# Esquema20.net
KiCad netlist of a schematic drawn in EAGLE
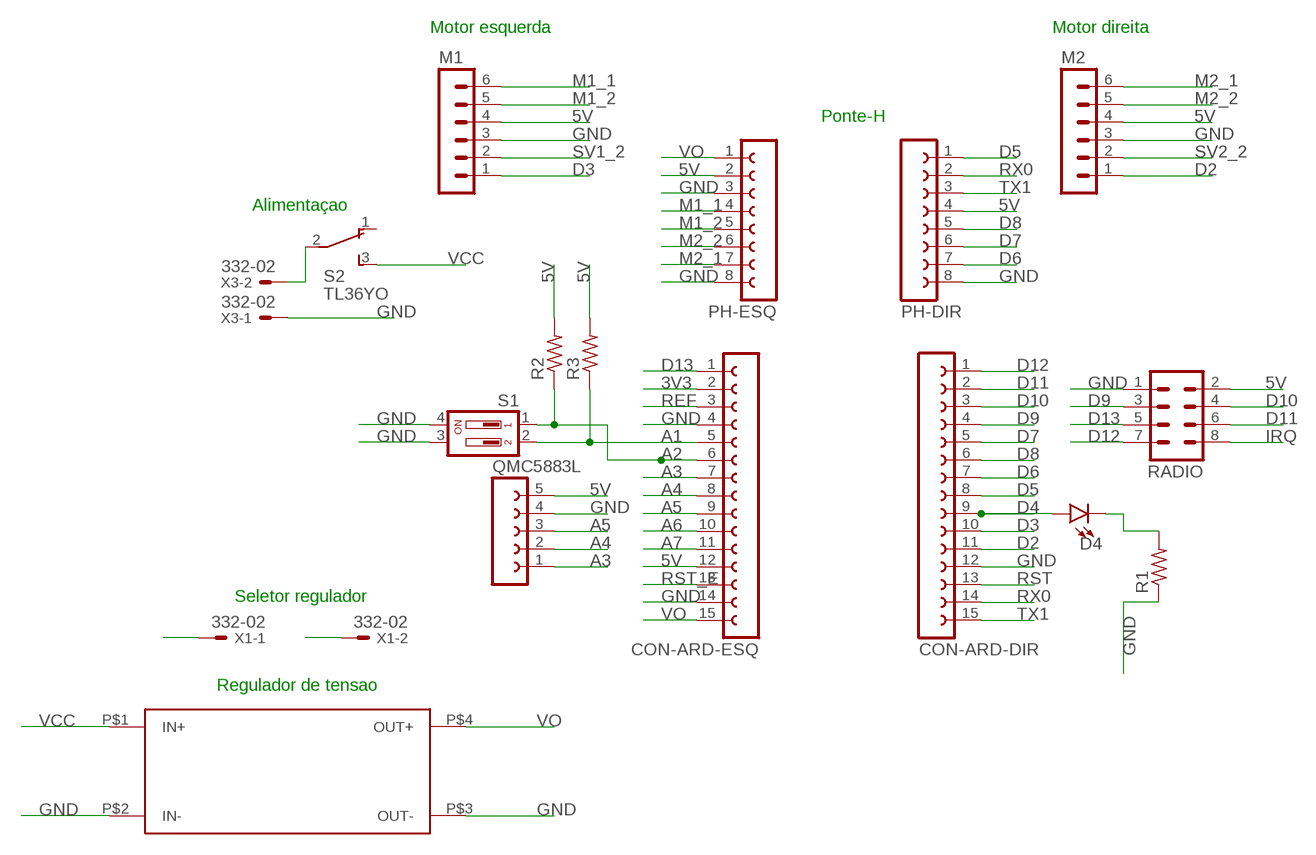
[diagram p0: schematic, sheet 1]

(export (version "E")
  (design (tool "Eeschema 10.0.6"))
  (components
    (comp (ref "CON-ARD-DIR")
      (value "FE15-1")
      (footprint "eagle-import:FE15")
      (libsource (lib "eagle-import") (part "FE15-1"))
    )
    (comp (ref "CON-ARD-ESQ")
      (value "FE15-1")
      (footprint "eagle-import:FE15")
      (fields (field (name "SPICEPREFIX") "X"))
      (libsource (lib "eagle-import") (part "FE15-1"))
    )
    (comp (ref "D4")
      (value "LED-3MM-NO_SILK")
      (footprint "eagle-import:LED_3MM-NS")
      (libsource (lib "eagle-import") (part "LED-3MM-NO_SILK"))
    )
    (comp (ref "M1")
      (value "MA06-1")
      (footprint "eagle-import:MA06-1")
      (libsource (lib "eagle-import") (part "MA06-1"))
    )
    (comp (ref "M2")
      (value "MA06-1")
      (footprint "eagle-import:MA06-1")
      (libsource (lib "eagle-import") (part "MA06-1"))
    )
    (comp (ref "PH-DIR")
      (value "FE08-1")
      (footprint "eagle-import:FE08")
      (libsource (lib "eagle-import") (part "FE08-1"))
    )
    (comp (ref "PH-ESQ")
      (value "FE08-1")
      (footprint "eagle-import:FE08")
      (libsource (lib "eagle-import") (part "FE08-1"))
    )
    (comp (ref "QMC5883L")
      (value "FE05W")
      (footprint "eagle-import:FE05W")
      (libsource (lib "eagle-import") (part "FE05W"))
    )
    (comp (ref "R1")
      (value "R-US_0207/12")
      (footprint "eagle-import:0207_12")
      (libsource (lib "eagle-import") (part "R-US_0207/12"))
    )
    (comp (ref "R2")
      (value "R-US_0207/12")
      (footprint "eagle-import:0207_12")
      (libsource (lib "eagle-import") (part "R-US_0207/12"))
    )
    (comp (ref "R3")
      (value "R-US_0207/12")
      (footprint "eagle-import:0207_12")
      (libsource (lib "eagle-import") (part "R-US_0207/12"))
    )
    (comp (ref "RADIO")
      (value "MA04-2")
      (footprint "eagle-import:MA04-2")
      (libsource (lib "eagle-import") (part "MA04-2"))
    )
    (comp (ref "S1")
      (value "DA02")
      (footprint "eagle-import:DA-02")
      (libsource (lib "eagle-import") (part "DA02"))
    )
    (comp (ref "S2")
      (value "TL36YO")
      (footprint "eagle-import:TL3XYO")
      (libsource (lib "eagle-import") (part "TL36YO"))
    )
    (comp (ref "U$1")
      (value "REGULADOR")
      (footprint "eagle-import:REGULADOR-FP")
      (libsource (lib "eagle-import") (part "REGULADOR"))
    )
    (comp (ref "X1")
      (value "332-02")
      (footprint "eagle-import:332-02")
      (libsource (lib "eagle-import") (part "332-02"))
    )
    (comp (ref "X3")
      (value "332-02")
      (footprint "eagle-import:332-02")
      (libsource (lib "eagle-import") (part "332-02"))
    )
  )
  (nets
    (net (code "1") (name "/3V3") (class "Default")
      (node (ref "CON-ARD-ESQ") (pin "2") (pinfunction "2_2") (pintype "passive"))
    )
    (net (code "2") (name "/5V") (class "Default")
      (node (ref "CON-ARD-ESQ") (pin "12") (pinfunction "12_12") (pintype "passive"))
      (node (ref "M1") (pin "4") (pinfunction "4_4") (pintype "passive"))
      (node (ref "M2") (pin "4") (pinfunction "4_4") (pintype "passive"))
      (node (ref "PH-DIR") (pin "4") (pinfunction "4_4") (pintype "passive"))
      (node (ref "PH-ESQ") (pin "2") (pinfunction "2_2") (pintype "passive"))
      (node (ref "QMC5883L") (pin "5") (pinfunction "5_5") (pintype "passive"))
      (node (ref "R2") (pin "2") (pinfunction "2_2") (pintype "passive"))
      (node (ref "R3") (pin "2") (pinfunction "2_2") (pintype "passive"))
      (node (ref "RADIO") (pin "2") (pinfunction "2_2") (pintype "passive"))
    )
    (net (code "3") (name "/A1") (class "Default")
      (node (ref "CON-ARD-ESQ") (pin "5") (pinfunction "5_5") (pintype "passive"))
      (node (ref "R3") (pin "1") (pinfunction "1_1") (pintype "passive"))
      (node (ref "S1") (pin "2") (pinfunction "2_2") (pintype "passive"))
    )
    (net (code "4") (name "/A2") (class "Default")
      (node (ref "CON-ARD-ESQ") (pin "6") (pinfunction "6_6") (pintype "passive"))
      (node (ref "R2") (pin "1") (pinfunction "1_1") (pintype "passive"))
      (node (ref "S1") (pin "1") (pinfunction "1_1") (pintype "passive"))
    )
    (net (code "5") (name "/A3") (class "Default")
      (node (ref "CON-ARD-ESQ") (pin "7") (pinfunction "7_7") (pintype "passive"))
      (node (ref "QMC5883L") (pin "1") (pinfunction "1_1") (pintype "passive"))
    )
    (net (code "6") (name "/A4") (class "Default")
      (node (ref "CON-ARD-ESQ") (pin "8") (pinfunction "8_8") (pintype "passive"))
      (node (ref "QMC5883L") (pin "2") (pinfunction "2_2") (pintype "passive"))
    )
    (net (code "7") (name "/A5") (class "Default")
      (node (ref "CON-ARD-ESQ") (pin "9") (pinfunction "9_9") (pintype "passive"))
      (node (ref "QMC5883L") (pin "3") (pinfunction "3_3") (pintype "passive"))
    )
    (net (code "8") (name "/A6") (class "Default")
      (node (ref "CON-ARD-ESQ") (pin "10") (pinfunction "10_10") (pintype "passive"))
    )
    (net (code "9") (name "/A7") (class "Default")
      (node (ref "CON-ARD-ESQ") (pin "11") (pinfunction "11_11") (pintype "passive"))
    )
    (net (code "10") (name "/D2") (class "Default")
      (node (ref "CON-ARD-DIR") (pin "11") (pinfunction "11_11") (pintype "passive"))
      (node (ref "M2") (pin "1") (pinfunction "1_1") (pintype "passive"))
    )
    (net (code "11") (name "/D3") (class "Default")
      (node (ref "CON-ARD-DIR") (pin "10") (pinfunction "10_10") (pintype "passive"))
      (node (ref "M1") (pin "1") (pinfunction "1_1") (pintype "passive"))
    )
    (net (code "12") (name "/D4") (class "Default")
      (node (ref "CON-ARD-DIR") (pin "9") (pinfunction "9_9") (pintype "passive"))
      (node (ref "D4") (pin "A") (pinfunction "A_A") (pintype "passive"))
    )
    (net (code "13") (name "/D5") (class "Default")
      (node (ref "CON-ARD-DIR") (pin "8") (pinfunction "8_8") (pintype "passive"))
      (node (ref "PH-DIR") (pin "1") (pinfunction "1_1") (pintype "passive"))
    )
    (net (code "14") (name "/D6") (class "Default")
      (node (ref "CON-ARD-DIR") (pin "7") (pinfunction "7_7") (pintype "passive"))
      (node (ref "PH-DIR") (pin "7") (pinfunction "7_7") (pintype "passive"))
    )
    (net (code "15") (name "/D7") (class "Default")
      (node (ref "CON-ARD-DIR") (pin "5") (pinfunction "5_5") (pintype "passive"))
      (node (ref "PH-DIR") (pin "6") (pinfunction "6_6") (pintype "passive"))
    )
    (net (code "16") (name "/D8") (class "Default")
      (node (ref "CON-ARD-DIR") (pin "6") (pinfunction "6_6") (pintype "passive"))
      (node (ref "PH-DIR") (pin "5") (pinfunction "5_5") (pintype "passive"))
    )
    (net (code "17") (name "/D9") (class "Default")
      (node (ref "CON-ARD-DIR") (pin "4") (pinfunction "4_4") (pintype "passive"))
      (node (ref "RADIO") (pin "3") (pinfunction "3_3") (pintype "passive"))
    )
    (net (code "18") (name "/D10") (class "Default")
      (node (ref "CON-ARD-DIR") (pin "3") (pinfunction "3_3") (pintype "passive"))
      (node (ref "RADIO") (pin "4") (pinfunction "4_4") (pintype "passive"))
    )
    (net (code "19") (name "/D11") (class "Default")
      (node (ref "CON-ARD-DIR") (pin "2") (pinfunction "2_2") (pintype "passive"))
      (node (ref "RADIO") (pin "6") (pinfunction "6_6") (pintype "passive"))
    )
    (net (code "20") (name "/D12") (class "Default")
      (node (ref "CON-ARD-DIR") (pin "1") (pinfunction "1_1") (pintype "passive"))
      (node (ref "RADIO") (pin "7") (pinfunction "7_7") (pintype "passive"))
    )
    (net (code "21") (name "/D13") (class "Default")
      (node (ref "CON-ARD-ESQ") (pin "1") (pinfunction "1_1") (pintype "passive"))
      (node (ref "RADIO") (pin "5") (pinfunction "5_5") (pintype "passive"))
    )
    (net (code "22") (name "/GND") (class "Default")
      (node (ref "CON-ARD-DIR") (pin "12") (pinfunction "12_12") (pintype "passive"))
      (node (ref "CON-ARD-ESQ") (pin "14") (pinfunction "14_14") (pintype "passive"))
      (node (ref "CON-ARD-ESQ") (pin "4") (pinfunction "4_4") (pintype "passive"))
      (node (ref "M1") (pin "3") (pinfunction "3_3") (pintype "passive"))
      (node (ref "M2") (pin "3") (pinfunction "3_3") (pintype "passive"))
      (node (ref "PH-DIR") (pin "8") (pinfunction "8_8") (pintype "passive"))
      (node (ref "PH-ESQ") (pin "3") (pinfunction "3_3") (pintype "passive"))
      (node (ref "PH-ESQ") (pin "8") (pinfunction "8_8") (pintype "passive"))
      (node (ref "QMC5883L") (pin "4") (pinfunction "4_4") (pintype "passive"))
      (node (ref "R1") (pin "1") (pinfunction "1_1") (pintype "passive"))
      (node (ref "RADIO") (pin "1") (pinfunction "1_1") (pintype "passive"))
      (node (ref "S1") (pin "3") (pinfunction "3_3") (pintype "passive"))
      (node (ref "S1") (pin "4") (pinfunction "4_4") (pintype "passive"))
      (node (ref "U$1") (pin "P$2") (pinfunction "IN-_P$2") (pintype "bidirectional"))
      (node (ref "U$1") (pin "P$3") (pinfunction "OUT-_P$3") (pintype "bidirectional"))
      (node (ref "X3") (pin "1") (pinfunction "S_1") (pintype "passive"))
    )
    (net (code "23") (name "/IRQ") (class "Default")
      (node (ref "RADIO") (pin "8") (pinfunction "8_8") (pintype "passive"))
    )
    (net (code "24") (name "/M1_1") (class "Default")
      (node (ref "M1") (pin "6") (pinfunction "6_6") (pintype "passive"))
      (node (ref "PH-ESQ") (pin "4") (pinfunction "4_4") (pintype "passive"))
    )
    (net (code "25") (name "/M1_2") (class "Default")
      (node (ref "M1") (pin "5") (pinfunction "5_5") (pintype "passive"))
      (node (ref "PH-ESQ") (pin "5") (pinfunction "5_5") (pintype "passive"))
    )
    (net (code "26") (name "/M2_1") (class "Default")
      (node (ref "M2") (pin "6") (pinfunction "6_6") (pintype "passive"))
      (node (ref "PH-ESQ") (pin "7") (pinfunction "7_7") (pintype "passive"))
    )
    (net (code "27") (name "/M2_2") (class "Default")
      (node (ref "M2") (pin "5") (pinfunction "5_5") (pintype "passive"))
      (node (ref "PH-ESQ") (pin "6") (pinfunction "6_6") (pintype "passive"))
    )
    (net (code "28") (name "/REF") (class "Default")
      (node (ref "CON-ARD-ESQ") (pin "3") (pinfunction "3_3") (pintype "passive"))
    )
    (net (code "29") (name "/RST") (class "Default")
      (node (ref "CON-ARD-DIR") (pin "13") (pinfunction "13_13") (pintype "passive"))
    )
    (net (code "30") (name "/RST_E") (class "Default")
      (node (ref "CON-ARD-ESQ") (pin "13") (pinfunction "13_13") (pintype "passive"))
    )
    (net (code "31") (name "/RX0") (class "Default")
      (node (ref "CON-ARD-DIR") (pin "14") (pinfunction "14_14") (pintype "passive"))
      (node (ref "PH-DIR") (pin "2") (pinfunction "2_2") (pintype "passive"))
    )
    (net (code "32") (name "/SV1_2") (class "Default")
      (node (ref "M1") (pin "2") (pinfunction "2_2") (pintype "passive"))
    )
    (net (code "33") (name "/SV2_2") (class "Default")
      (node (ref "M2") (pin "2") (pinfunction "2_2") (pintype "passive"))
    )
    (net (code "34") (name "/TX1") (class "Default")
      (node (ref "CON-ARD-DIR") (pin "15") (pinfunction "15_15") (pintype "passive"))
      (node (ref "PH-DIR") (pin "3") (pinfunction "3_3") (pintype "passive"))
    )
    (net (code "35") (name "/VCC") (class "Default")
      (node (ref "S2") (pin "3") (pinfunction "S_3") (pintype "passive"))
      (node (ref "U$1") (pin "P$1") (pinfunction "IN+_P$1") (pintype "bidirectional"))
      (node (ref "X1") (pin "1") (pinfunction "S_1") (pintype "passive"))
    )
    (net (code "36") (name "/VO") (class "Default")
      (node (ref "CON-ARD-ESQ") (pin "15") (pinfunction "15_15") (pintype "passive"))
      (node (ref "PH-ESQ") (pin "1") (pinfunction "1_1") (pintype "passive"))
      (node (ref "U$1") (pin "P$4") (pinfunction "OUT+_P$4") (pintype "bidirectional"))
      (node (ref "X1") (pin "2") (pinfunction "S_2") (pintype "passive"))
    )
    (net (code "37") (name "Net-(D4-C)") (class "Default")
      (node (ref "D4") (pin "K") (pinfunction "C_K") (pintype "passive"))
      (node (ref "R1") (pin "2") (pinfunction "2_2") (pintype "passive"))
    )
    (net (code "38") (name "Net-(S2-P)") (class "Default")
      (node (ref "S2") (pin "2") (pinfunction "P_2") (pintype "passive"))
      (node (ref "X3") (pin "2") (pinfunction "S_2") (pintype "passive"))
    )
    (net (code "39") (name "unconnected-(S2-O-Pad1)") (class "Default")
      (node (ref "S2") (pin "1") (pinfunction "O_1") (pintype "passive"))
    )
  )
)
